# DAC.net
KiCad netlist of a schematic drawn in Altium Designer
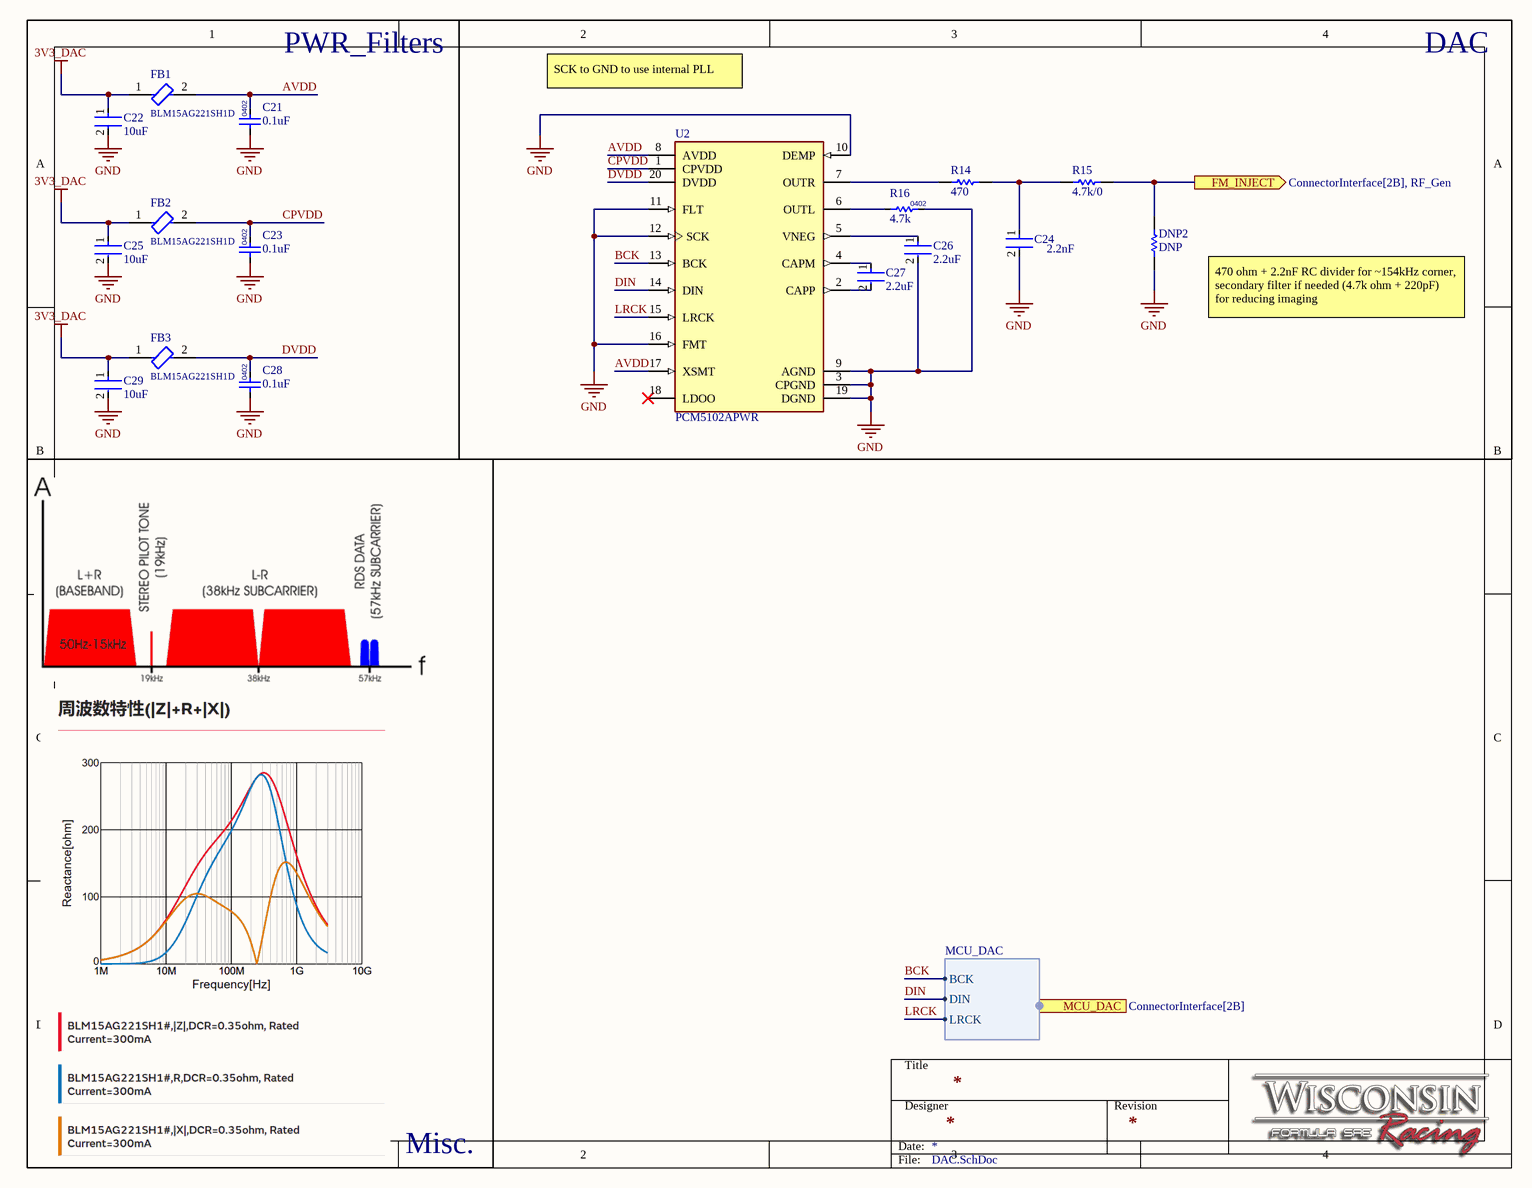
[diagram p0: DAC.SchDoc]

(export (version "E")
  (design (tool "Eeschema 10.0.6"))
  (components
    (comp (ref "C21")
      (value "0.1uF")
      (footprint "FP-CC0402-IPC_B")
      (fields (field (name "TOLERANCE") "10%"))
      (libsource (lib "University of Wisconsin Formula FSAE") (part "0402 ceramic cap"))
    )
    (comp (ref "C22")
      (value "10uF")
      (footprint "FP-C0402C106M9PACTU-MFG")
      (description "CAP CER 10UF 6.3V X5R 0402")
      (fields (field (name "TOLERANCE") "20%"))
      (libsource (lib "Altium Content Vault") (part "b4654b650e69147ec39a6b967a45e02"))
    )
    (comp (ref "C23")
      (value "0.1uF")
      (footprint "FP-CC0402-IPC_B")
      (fields (field (name "TOLERANCE") "10%"))
      (libsource (lib "University of Wisconsin Formula FSAE") (part "0402 ceramic cap"))
    )
    (comp (ref "C24")
      (value "2.2nF")
      (footprint "FP-GRM155-0_05-IPC_C")
      (description "Chip Multilayer Ceramic Capacitors for General Purpose, 0402, 2200pF, C0G, 30ppm/°C, 5%, 50V")
      (libsource (lib "Altium Content Vault") (part "02cd4be3c70576c341d710602a673aa"))
    )
    (comp (ref "C25")
      (value "10uF")
      (footprint "FP-C0402C106M9PACTU-MFG")
      (description "CAP CER 10UF 6.3V X5R 0402")
      (fields (field (name "TOLERANCE") "20%"))
      (libsource (lib "Altium Content Vault") (part "b4654b650e69147ec39a6b967a45e02"))
    )
    (comp (ref "C26")
      (value "2.2uF")
      (footprint "FP-GRM155-0_2-IPC_B")
      (description "Chip Multilayer Ceramic Capacitors for General Purpose, 0402, 2.2uF, X7R, 15%, 10%, 10V")
      (libsource (lib "Altium Content Vault") (part "b4654b650e69147ec39a6b967a45e02"))
    )
    (comp (ref "C27")
      (value "2.2uF")
      (footprint "FP-GRM155-0_2-IPC_B")
      (description "Chip Multilayer Ceramic Capacitors for General Purpose, 0402, 2.2uF, X7R, 15%, 10%, 10V")
      (libsource (lib "Altium Content Vault") (part "b4654b650e69147ec39a6b967a45e02"))
    )
    (comp (ref "C28")
      (value "0.1uF")
      (footprint "FP-CC0402-IPC_B")
      (fields (field (name "TOLERANCE") "10%"))
      (libsource (lib "University of Wisconsin Formula FSAE") (part "0402 ceramic cap"))
    )
    (comp (ref "C29")
      (value "10uF")
      (footprint "FP-C0402C106M9PACTU-MFG")
      (description "CAP CER 10UF 6.3V X5R 0402")
      (fields (field (name "TOLERANCE") "20%"))
      (libsource (lib "Altium Content Vault") (part "b4654b650e69147ec39a6b967a45e02"))
    )
    (comp (ref "DNP2")
      (value "DNP")
      (footprint "RESC1005X40X25NL05T10")
      (fields (field (name "MANUFACTURER") "Yageo / Phycomp") (field (name "PART NUMBER") "RC0402JR-070RL"))
      (libsource (lib "Altium Content Vault") (part "RES"))
    )
    (comp (ref "FB1")
      (value "BLM15AG221SH1D")
      (footprint "FP-BLM15-0_05-MFG")
      (description "Chip Ferrite Bead, 0402, 220Ω @ 100MHz, 0.35Ω, 25%, 300mA")
      (fields (field (name "TOLERANCE") "25%"))
      (libsource (lib "Altium Content Vault") (part "5f30dd21d616792df468990f7003faa"))
    )
    (comp (ref "FB2")
      (value "BLM15AG221SH1D")
      (footprint "FP-BLM15-0_05-MFG")
      (description "Chip Ferrite Bead, 0402, 220Ω @ 100MHz, 0.35Ω, 25%, 300mA")
      (fields (field (name "TOLERANCE") "25%"))
      (libsource (lib "Altium Content Vault") (part "5f30dd21d616792df468990f7003faa"))
    )
    (comp (ref "FB3")
      (value "BLM15AG221SH1D")
      (footprint "FP-BLM15-0_05-MFG")
      (description "Chip Ferrite Bead, 0402, 220Ω @ 100MHz, 0.35Ω, 25%, 300mA")
      (fields (field (name "TOLERANCE") "25%"))
      (libsource (lib "Altium Content Vault") (part "5f30dd21d616792df468990f7003faa"))
    )
    (comp (ref "R14")
      (value "470")
      (footprint "RESC1005X40X25ML05T10")
      (fields (field (name "PART NUMBER") "RC0402FR-07470RL") (field (name "MANUFACTURER") "Yageo / Phycomp"))
      (libsource (lib "Altium Content Vault") (part "RES"))
    )
    (comp (ref "R15")
      (value "4.7k/0")
      (footprint "RESC1005X40X25NL05T10")
      (fields (field (name "MANUFACTURER") "Yageo / Phycomp") (field (name "PART NUMBER") "RC0402JR-070RL"))
      (libsource (lib "Altium Content Vault") (part "RES"))
    )
    (comp (ref "R16")
      (value "4.7k")
      (footprint "RESC1005X40X25NL05T10")
      (description "Res General Purpose Thick Film 0402 4.7K Ohm 1% 1/16W ±100ppm/°C Molded SMD Paper T/R")
      (fields (field (name "TOLERANCE") "1%") (field (name "Comment") "4.7k 1%"))
      (libsource (lib "University of Wisconsin Formula FSAE") (part "RES"))
    )
    (comp (ref "U2")
      (value "PCM5102APWR")
      (footprint "FP-PW0020A-IPC_A")
      (description "IC DAC 16/24/32BIT 384K 20TSSOP")
      (libsource (lib "Altium Content Vault") (part "831166dc95f78e7a0e4986cce343839"))
    )
  )
  (nets
    (net (code "2") (name "/AVDD") (class "Default")
      (node (ref "C21") (pin "2") (pinfunction "2_2") (pintype "passive"))
      (node (ref "FB1") (pin "2") (pinfunction "2_2") (pintype "passive"))
      (node (ref "U2") (pin "17") (pinfunction "XSMT_17") (pintype "input"))
      (node (ref "U2") (pin "8") (pinfunction "AVDD_8") (pintype "power_in"))
    )
    (net (code "3") (name "/BCK") (class "Default")
      (node (ref "U2") (pin "13") (pinfunction "BCK_13") (pintype "input"))
    )
    (net (code "4") (name "/CPVDD") (class "Default")
      (node (ref "C23") (pin "2") (pinfunction "2_2") (pintype "passive"))
      (node (ref "FB2") (pin "2") (pinfunction "2_2") (pintype "passive"))
      (node (ref "U2") (pin "1") (pinfunction "CPVDD_1") (pintype "power_in"))
    )
    (net (code "5") (name "/DIN") (class "Default")
      (node (ref "U2") (pin "14") (pinfunction "DIN_14") (pintype "input"))
    )
    (net (code "6") (name "/DVDD") (class "Default")
      (node (ref "C28") (pin "2") (pinfunction "2_2") (pintype "passive"))
      (node (ref "FB3") (pin "2") (pinfunction "2_2") (pintype "passive"))
      (node (ref "U2") (pin "20") (pinfunction "DVDD_20") (pintype "power_in"))
    )
    (net (code "7") (name "/FM_INJECT") (class "Default")
      (node (ref "DNP2") (pin "2") (pinfunction "2_2") (pintype "passive"))
      (node (ref "R15") (pin "2") (pinfunction "2_2") (pintype "passive"))
    )
    (net (code "8") (name "/LRCK") (class "Default")
      (node (ref "U2") (pin "15") (pinfunction "LRCK_15") (pintype "input"))
    )
    (net (code "10") (name "3V3_DAC") (class "Default")
      (node (ref "C22") (pin "1") (pinfunction "1_1") (pintype "passive"))
      (node (ref "C25") (pin "1") (pinfunction "1_1") (pintype "passive"))
      (node (ref "C29") (pin "1") (pinfunction "1_1") (pintype "passive"))
      (node (ref "FB1") (pin "1") (pinfunction "1_1") (pintype "passive"))
      (node (ref "FB2") (pin "1") (pinfunction "1_1") (pintype "passive"))
      (node (ref "FB3") (pin "1") (pinfunction "1_1") (pintype "passive"))
    )
    (net (code "11") (name "GND") (class "Default")
      (node (ref "C21") (pin "1") (pinfunction "1_1") (pintype "passive"))
      (node (ref "C22") (pin "2") (pinfunction "2_2") (pintype "passive"))
      (node (ref "C23") (pin "1") (pinfunction "1_1") (pintype "passive"))
      (node (ref "C24") (pin "2") (pinfunction "2_2") (pintype "passive"))
      (node (ref "C25") (pin "2") (pinfunction "2_2") (pintype "passive"))
      (node (ref "C26") (pin "2") (pinfunction "2_2") (pintype "passive"))
      (node (ref "C28") (pin "1") (pinfunction "1_1") (pintype "passive"))
      (node (ref "C29") (pin "2") (pinfunction "2_2") (pintype "passive"))
      (node (ref "DNP2") (pin "1") (pinfunction "1_1") (pintype "passive"))
      (node (ref "R16") (pin "2") (pinfunction "2_2") (pintype "passive"))
      (node (ref "U2") (pin "10") (pinfunction "DEMP_10") (pintype "input"))
      (node (ref "U2") (pin "11") (pinfunction "FLT_11") (pintype "input"))
      (node (ref "U2") (pin "12") (pinfunction "SCK_12") (pintype "input"))
      (node (ref "U2") (pin "16") (pinfunction "FMT_16") (pintype "input"))
      (node (ref "U2") (pin "19") (pinfunction "DGND_19") (pintype "power_in"))
      (node (ref "U2") (pin "3") (pinfunction "CPGND_3") (pintype "power_in"))
      (node (ref "U2") (pin "9") (pinfunction "AGND_9") (pintype "power_in"))
    )
    (net (code "12") (name "Net-(C24-Pad1)") (class "Default")
      (node (ref "C24") (pin "1") (pinfunction "1_1") (pintype "passive"))
      (node (ref "R14") (pin "2") (pinfunction "2_2") (pintype "passive"))
      (node (ref "R15") (pin "1") (pinfunction "1_1") (pintype "passive"))
    )
    (net (code "13") (name "Net-(U2-CAPM)") (class "Default")
      (node (ref "C27") (pin "1") (pinfunction "1_1") (pintype "passive"))
      (node (ref "U2") (pin "4") (pinfunction "CAPM_4") (pintype "output"))
    )
    (net (code "14") (name "Net-(U2-CAPP)") (class "Default")
      (node (ref "C27") (pin "2") (pinfunction "2_2") (pintype "passive"))
      (node (ref "U2") (pin "2") (pinfunction "CAPP_2") (pintype "output"))
    )
    (net (code "15") (name "Net-(U2-OUTL)") (class "Default")
      (node (ref "R16") (pin "1") (pinfunction "1_1") (pintype "passive"))
      (node (ref "U2") (pin "6") (pinfunction "OUTL_6") (pintype "passive"))
    )
    (net (code "16") (name "Net-(U2-OUTR)") (class "Default")
      (node (ref "R14") (pin "1") (pinfunction "1_1") (pintype "passive"))
      (node (ref "U2") (pin "7") (pinfunction "OUTR_7") (pintype "passive"))
    )
    (net (code "17") (name "Net-(U2-VNEG)") (class "Default")
      (node (ref "C26") (pin "1") (pinfunction "1_1") (pintype "passive"))
      (node (ref "U2") (pin "5") (pinfunction "VNEG_5") (pintype "output"))
    )
    (net (code "18") (name "unconnected-(U2-LDOO-Pad18)") (class "Default")
      (node (ref "U2") (pin "18") (pinfunction "LDOO_18") (pintype "power_in+no_connect"))
    )
  )
)
